# Controller_low_power_v1_0.net
KiCad netlist of a schematic drawn in EAGLE
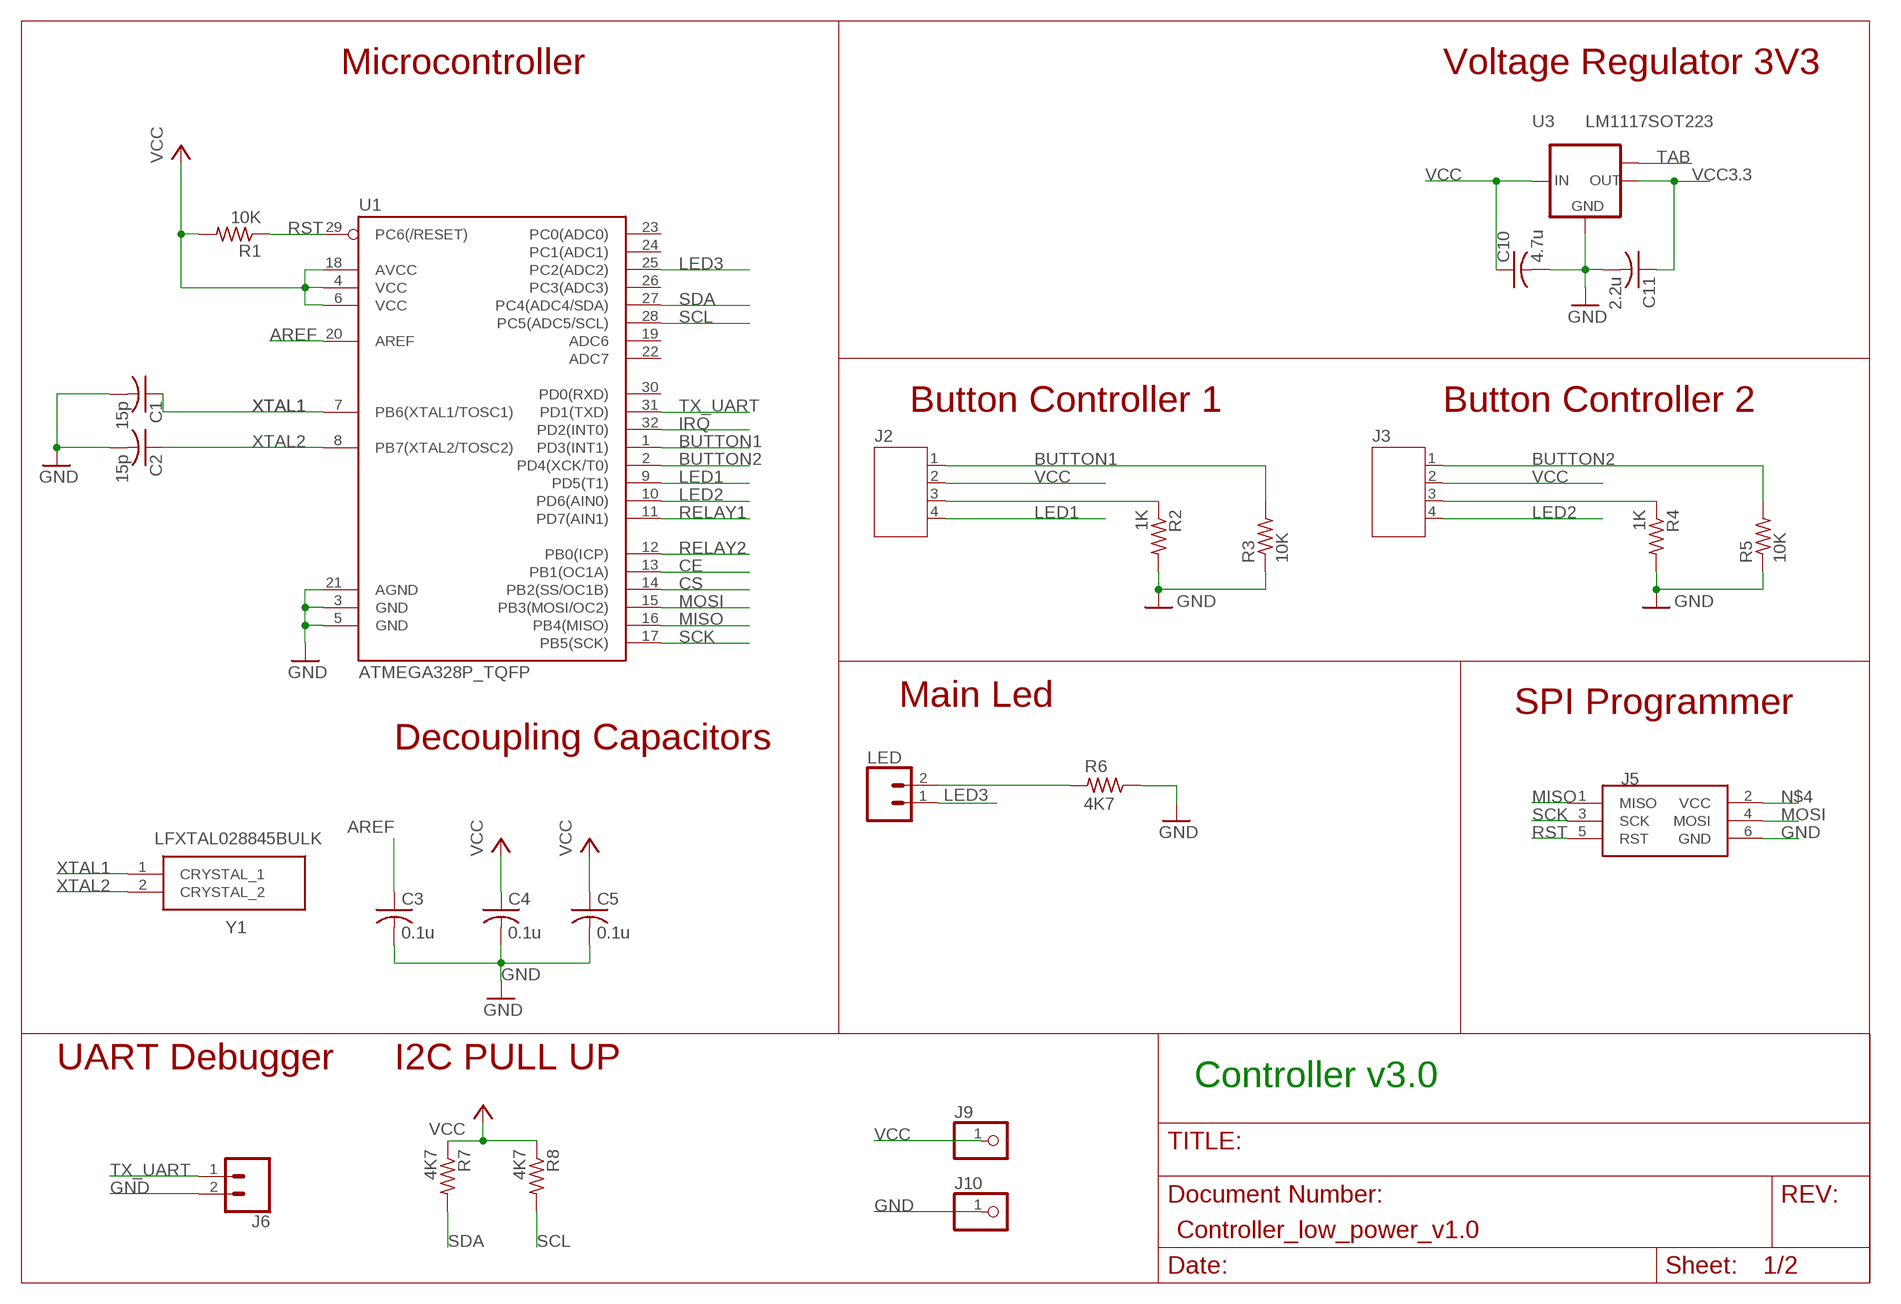
[diagram p0: schematic, sheet 1]
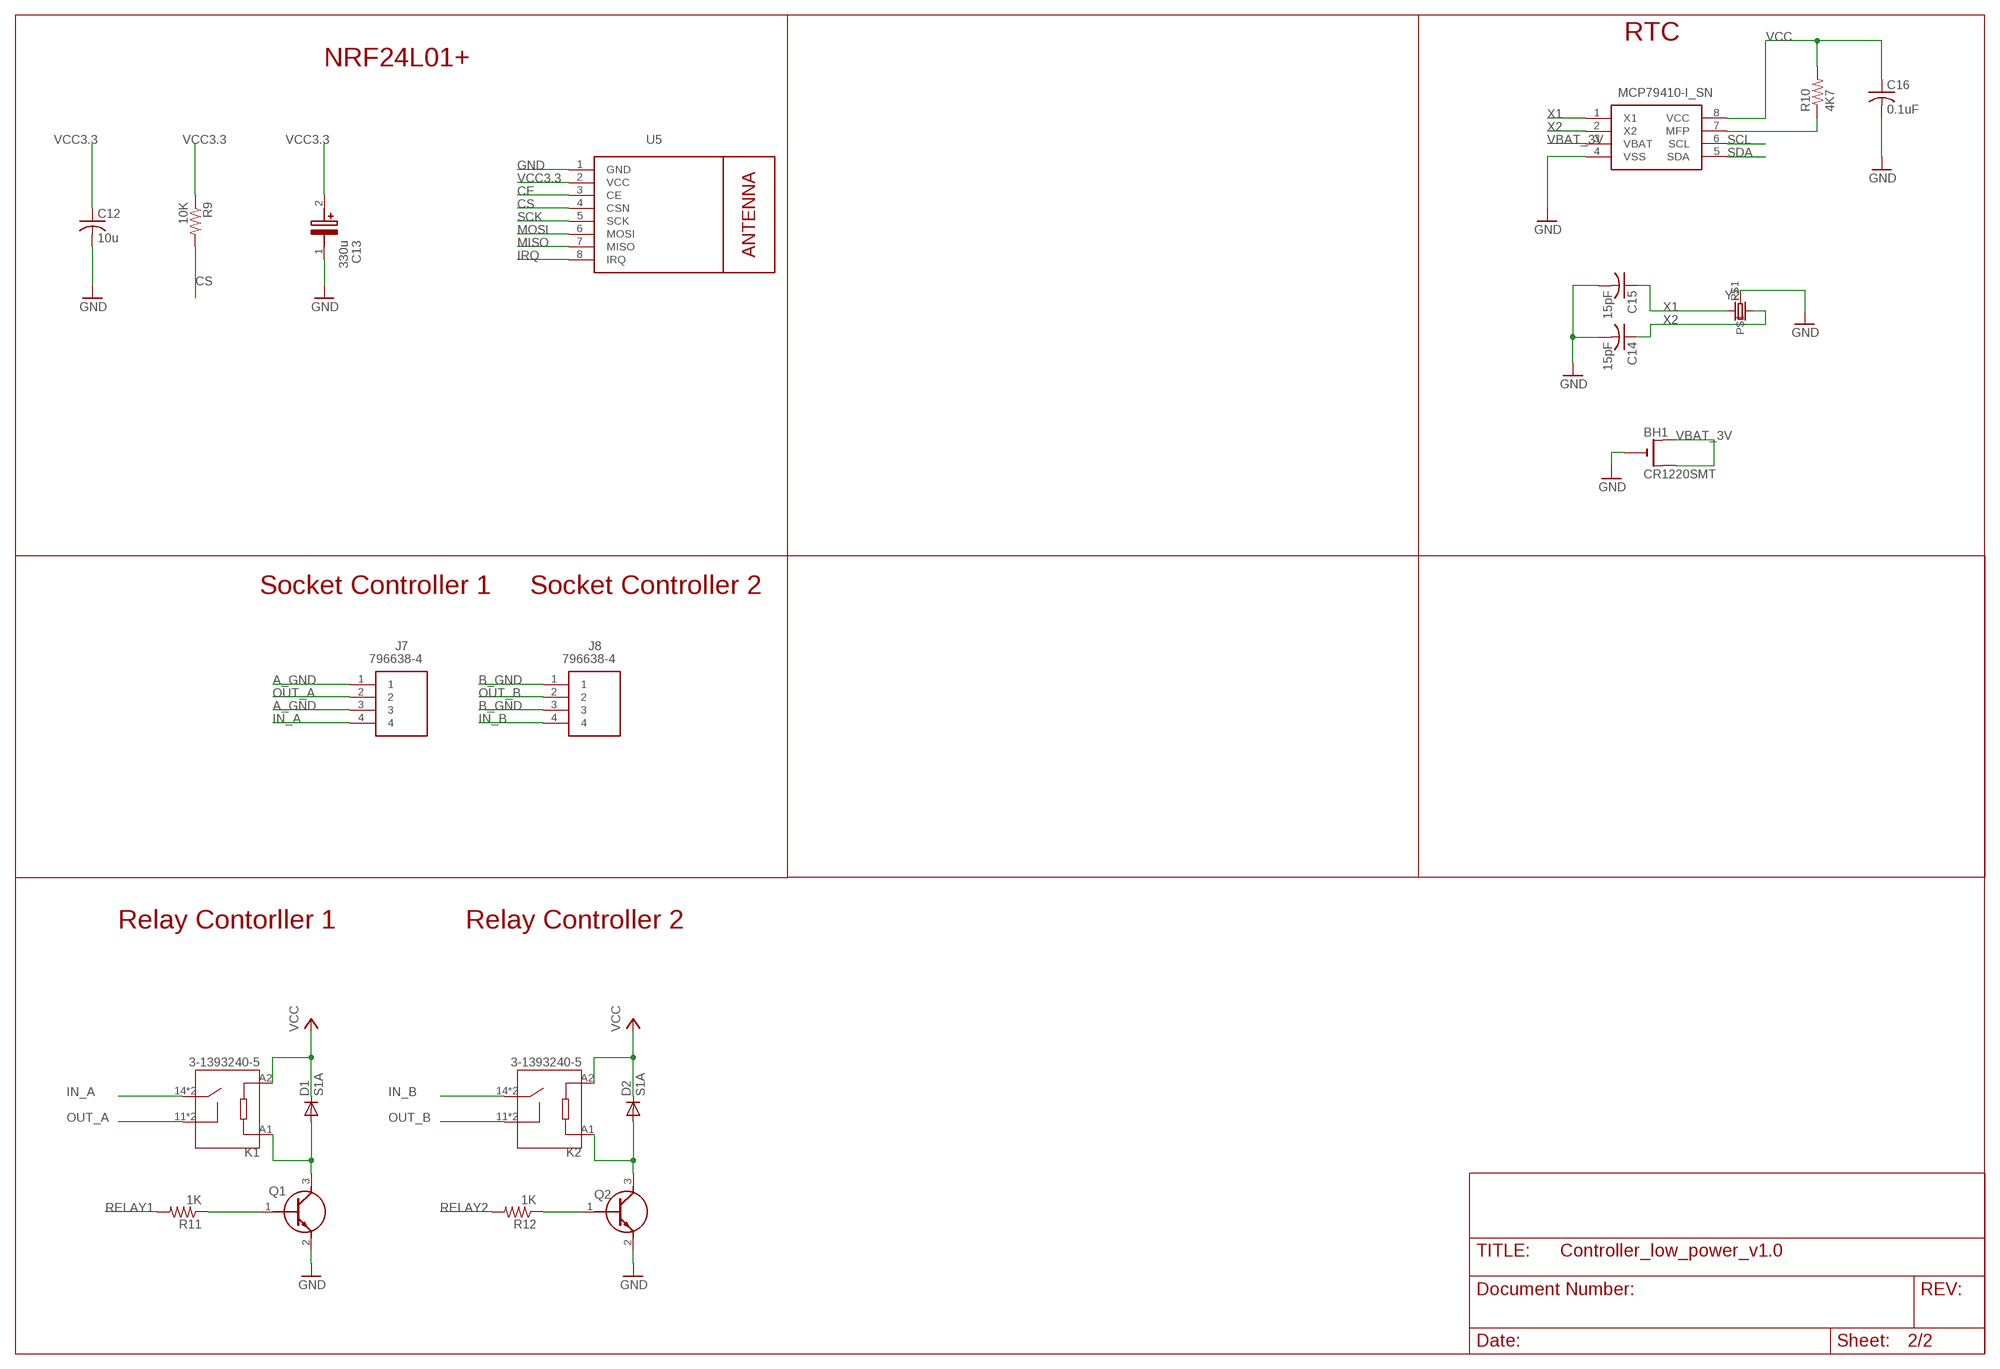
[diagram p1: schematic, sheet 2]

(export (version "E")
  (design (tool "Eeschema 10.0.6"))
  (components
    (comp (ref "C1")
      (value "15p")
      (footprint "eagle-import:SMD-0805")
      (libsource (lib "eagle-import") (part "CAPACITOR-SMD-0805"))
    )
    (comp (ref "C2")
      (value "15p")
      (footprint "eagle-import:SMD-0805")
      (libsource (lib "eagle-import") (part "CAPACITOR-SMD-0805"))
    )
    (comp (ref "C3")
      (value "0.1u")
      (footprint "eagle-import:SMD-0805")
      (libsource (lib "eagle-import") (part "CAPACITOR-SMD-0805"))
    )
    (comp (ref "C4")
      (value "0.1u")
      (footprint "eagle-import:SMD-0805")
      (libsource (lib "eagle-import") (part "CAPACITOR-SMD-0805"))
    )
    (comp (ref "C5")
      (value "0.1u")
      (footprint "eagle-import:SMD-0805")
      (libsource (lib "eagle-import") (part "CAPACITOR-SMD-0805"))
    )
    (comp (ref "C10")
      (value "4.7u")
      (footprint "eagle-import:SMD-0805")
      (libsource (lib "eagle-import") (part "CAPACITOR-SMD-0805"))
    )
    (comp (ref "C11")
      (value "2.2u")
      (footprint "eagle-import:SMD-0805")
      (libsource (lib "eagle-import") (part "CAPACITOR-SMD-0805"))
    )
    (comp (ref "J2")
      (value "JST-PH4")
      (footprint "eagle-import:JST-PH4")
      (libsource (lib "eagle-import") (part "JST-PH4"))
    )
    (comp (ref "J3")
      (value "JST-PH4")
      (footprint "eagle-import:JST-PH4")
      (libsource (lib "eagle-import") (part "JST-PH4"))
    )
    (comp (ref "J5")
      (value "ISP")
      (footprint "eagle-import:AVRISP")
      (libsource (lib "eagle-import") (part "AVRISP-6"))
    )
    (comp (ref "J6")
      (value "CONN_02")
      (footprint "eagle-import:1X02")
      (libsource (lib "eagle-import") (part "CONN_02"))
    )
    (comp (ref "J9")
      (value "PINHD-1X1CB")
      (footprint "eagle-import:1X01-CLEANBIG")
      (libsource (lib "eagle-import") (part "PINHD-1X1CB"))
    )
    (comp (ref "J10")
      (value "PINHD-1X1CB")
      (footprint "eagle-import:1X01-CLEANBIG")
      (libsource (lib "eagle-import") (part "PINHD-1X1CB"))
    )
    (comp (ref "LED")
      (value "CONN_02")
      (footprint "eagle-import:1X02")
      (libsource (lib "eagle-import") (part "CONN_02"))
    )
    (comp (ref "R1")
      (value "10K")
      (footprint "eagle-import:SMD-0805")
      (libsource (lib "eagle-import") (part "RESISTOR-SMD-0805"))
    )
    (comp (ref "R2")
      (value "1K")
      (footprint "eagle-import:SMD-0805")
      (libsource (lib "eagle-import") (part "RESISTOR-SMD-0805"))
    )
    (comp (ref "R3")
      (value "10K")
      (footprint "eagle-import:SMD-0805")
      (libsource (lib "eagle-import") (part "RESISTOR-SMD-0805"))
    )
    (comp (ref "R4")
      (value "1K")
      (footprint "eagle-import:SMD-0805")
      (libsource (lib "eagle-import") (part "RESISTOR-SMD-0805"))
    )
    (comp (ref "R5")
      (value "10K")
      (footprint "eagle-import:SMD-0805")
      (libsource (lib "eagle-import") (part "RESISTOR-SMD-0805"))
    )
    (comp (ref "R6")
      (value "4K7")
      (footprint "eagle-import:SMD-0805")
      (libsource (lib "eagle-import") (part "RESISTOR-SMD-0805"))
    )
    (comp (ref "R7")
      (value "4K7")
      (footprint "eagle-import:SMD-0805")
      (libsource (lib "eagle-import") (part "RESISTOR-SMD-0805"))
    )
    (comp (ref "R8")
      (value "4K7")
      (footprint "eagle-import:SMD-0805")
      (libsource (lib "eagle-import") (part "RESISTOR-SMD-0805"))
    )
    (comp (ref "U1")
      (value "ATMEGA328P_TQFP")
      (footprint "eagle-import:TQFP32-08")
      (libsource (lib "eagle-import") (part "ATMEGA328P_TQFP"))
    )
    (comp (ref "U3")
      (value "LM1117SOT223")
      (footprint "eagle-import:SOT223")
      (libsource (lib "eagle-import") (part "LM1117MPX-3.3"))
    )
    (comp (ref "Y1")
      (value "LFXTAL028845BULK")
      (footprint "eagle-import:LFXTAL028845BULK")
      (libsource (lib "eagle-import") (part "LFXTAL028845BULK"))
    )
    (comp (ref "BH1")
      (value "CR1220SMT")
      (footprint "eagle-import:CR1220-SMD")
      (fields (field (name "MF") "FDK America,") (field (name "MP") "CR1220"))
      (libsource (lib "eagle-import") (part "CR1220SMT"))
    )
    (comp (ref "C12")
      (value "10u")
      (footprint "eagle-import:SMD-0805")
      (libsource (lib "eagle-import") (part "CAPACITOR-SMD-0805"))
    )
    (comp (ref "C13")
      (value "330u")
      (footprint "eagle-import:SMD_LYTIC_D8")
      (fields
        (field (name "MANUFACTURER_PART_NUMBER") "EEE-FNC271XUP")
        (field (name "MOUSER_PART_NUMBER") "667-EEE-FNC271XUP")
      )
      (libsource (lib "eagle-import") (part "EEE-FNC271XUP"))
    )
    (comp (ref "C14")
      (value "15pF")
      (footprint "eagle-import:SMD-0805")
      (libsource (lib "eagle-import") (part "CAPACITOR-SMD-0805"))
    )
    (comp (ref "C15")
      (value "15pF")
      (footprint "eagle-import:SMD-0805")
      (libsource (lib "eagle-import") (part "CAPACITOR-SMD-0805"))
    )
    (comp (ref "C16")
      (value "0.1uF")
      (footprint "eagle-import:SMD-0805")
      (libsource (lib "eagle-import") (part "CAPACITOR-SMD-0805"))
    )
    (comp (ref "D1")
      (value "S1A")
      (footprint "eagle-import:DO214AC")
      (fields (field (name "MF") "Fairchild"))
      (libsource (lib "eagle-import") (part "S1A"))
    )
    (comp (ref "D2")
      (value "S1A")
      (footprint "eagle-import:DO214AC")
      (fields (field (name "MF") "Fairchild"))
      (libsource (lib "eagle-import") (part "S1A"))
    )
    (comp (ref "J7")
      (value "796638-4")
      (footprint "eagle-import:SHDRRA4W102P0X508_1X4_2214X120")
      (fields (field (name "MOUSER_PART_NUMBER") "571-7966384"))
      (libsource (lib "eagle-import") (part "796638-4"))
    )
    (comp (ref "J8")
      (value "796638-4")
      (footprint "eagle-import:SHDRRA4W102P0X508_1X4_2214X120")
      (fields (field (name "MOUSER_PART_NUMBER") "571-7966384"))
      (libsource (lib "eagle-import") (part "796638-4"))
    )
    (comp (ref "K1")
      (value "3-1393240-5")
      (footprint "eagle-import:TE_3-1393240-5")
      (fields (field (name "MF") "TE Connectivity"))
      (libsource (lib "eagle-import") (part "3-1393240-5"))
    )
    (comp (ref "K2")
      (value "3-1393240-5")
      (footprint "eagle-import:TE_3-1393240-5")
      (fields (field (name "MF") "TE Connectivity"))
      (libsource (lib "eagle-import") (part "3-1393240-5"))
    )
    (comp (ref "Q1")
      (value "MMBT2222A-TP")
      (footprint "eagle-import:SI2305TP")
      (fields (field (name "MOUSER_PART_NUMBER") "833-MMBT2222A-TP"))
      (libsource (lib "eagle-import") (part "MMBT2222A-TP"))
    )
    (comp (ref "Q2")
      (value "MMBT2222A-TP")
      (footprint "eagle-import:SI2305TP")
      (fields (field (name "MOUSER_PART_NUMBER") "833-MMBT2222A-TP"))
      (libsource (lib "eagle-import") (part "MMBT2222A-TP"))
    )
    (comp (ref "R9")
      (value "10K")
      (footprint "eagle-import:SMD-0805")
      (libsource (lib "eagle-import") (part "RESISTOR-SMD-0805"))
    )
    (comp (ref "R10")
      (value "4K7")
      (footprint "eagle-import:SMD-0805")
      (libsource (lib "eagle-import") (part "RESISTOR-SMD-0805"))
    )
    (comp (ref "R11")
      (value "1K")
      (footprint "eagle-import:SMD-0805")
      (libsource (lib "eagle-import") (part "RESISTOR-SMD-0805"))
    )
    (comp (ref "R12")
      (value "1K")
      (footprint "eagle-import:SMD-0805")
      (libsource (lib "eagle-import") (part "RESISTOR-SMD-0805"))
    )
    (comp (ref "U5")
      (value "WIRELESS-NRF24L01")
      (footprint "eagle-import:WIRELESS-NRF24L01")
      (libsource (lib "eagle-import") (part "WIRELESS-NRF24L01"))
    )
    (comp (ref "U6")
      (value "MCP79410-I_SN")
      (footprint "eagle-import:SOIC127P600X175-8N")
      (fields
        (field (name "MANUFACTURER_PART_NUMBER") "MCP79410-I/SN")
        (field (name "MOUSER_PART_NUMBER") "579-MCP79410-I/SN")
      )
      (libsource (lib "eagle-import") (part "MCP79410-I_SN"))
    )
    (comp (ref "Y2")
      (value "CRYSTALTC26H")
      (footprint "eagle-import:TC26H")
      (libsource (lib "eagle-import") (part "CRYSTALTC26H"))
    )
  )
  (nets
    (net (code "1") (name "AREF") (class "Default")
      (node (ref "C3") (pin "1") (pinfunction "1_1") (pintype "passive"))
      (node (ref "U1") (pin "20") (pinfunction "AREF_20") (pintype "bidirectional"))
    )
    (net (code "2") (name "A_GND") (class "Default")
      (node (ref "J7") (pin "1") (pinfunction "1_1") (pintype "bidirectional"))
      (node (ref "J7") (pin "3") (pinfunction "3_3") (pintype "bidirectional"))
    )
    (net (code "3") (name "BUTTON1") (class "Default")
      (node (ref "J2") (pin "1") (pinfunction "1_1") (pintype "passive"))
      (node (ref "R3") (pin "2") (pinfunction "2_2") (pintype "passive"))
      (node (ref "U1") (pin "1") (pinfunction "PD3(INT1)_1") (pintype "bidirectional"))
    )
    (net (code "4") (name "BUTTON2") (class "Default")
      (node (ref "J3") (pin "1") (pinfunction "1_1") (pintype "passive"))
      (node (ref "R5") (pin "2") (pinfunction "2_2") (pintype "passive"))
      (node (ref "U1") (pin "2") (pinfunction "PD4(XCK/T0)_2") (pintype "bidirectional"))
    )
    (net (code "5") (name "B_GND") (class "Default")
      (node (ref "J8") (pin "1") (pinfunction "1_1") (pintype "bidirectional"))
      (node (ref "J8") (pin "3") (pinfunction "3_3") (pintype "bidirectional"))
    )
    (net (code "6") (name "CE") (class "Default")
      (node (ref "U1") (pin "13") (pinfunction "PB1(OC1A)_13") (pintype "bidirectional"))
      (node (ref "U5") (pin "3") (pinfunction "CE_3") (pintype "bidirectional"))
    )
    (net (code "7") (name "CS") (class "Default")
      (node (ref "R9") (pin "2") (pinfunction "2_2") (pintype "passive"))
      (node (ref "U1") (pin "14") (pinfunction "PB2(SS/OC1B)_14") (pintype "bidirectional"))
      (node (ref "U5") (pin "4") (pinfunction "CSN_4") (pintype "bidirectional"))
    )
    (net (code "8") (name "GND") (class "Default")
      (node (ref "BH1") (pin "-") (pinfunction "-_-") (pintype "passive"))
      (node (ref "C1") (pin "2") (pinfunction "2_2") (pintype "passive"))
      (node (ref "C10") (pin "2") (pinfunction "2_2") (pintype "passive"))
      (node (ref "C11") (pin "2") (pinfunction "2_2") (pintype "passive"))
      (node (ref "C12") (pin "2") (pinfunction "2_2") (pintype "passive"))
      (node (ref "C13") (pin "1") (pinfunction "1_1") (pintype "bidirectional"))
      (node (ref "C14") (pin "2") (pinfunction "2_2") (pintype "passive"))
      (node (ref "C15") (pin "2") (pinfunction "2_2") (pintype "passive"))
      (node (ref "C16") (pin "2") (pinfunction "2_2") (pintype "passive"))
      (node (ref "C2") (pin "2") (pinfunction "2_2") (pintype "passive"))
      (node (ref "C3") (pin "2") (pinfunction "2_2") (pintype "passive"))
      (node (ref "C4") (pin "2") (pinfunction "2_2") (pintype "passive"))
      (node (ref "C5") (pin "2") (pinfunction "2_2") (pintype "passive"))
      (node (ref "J10") (pin "1") (pinfunction "1_1") (pintype "passive"))
      (node (ref "J5") (pin "6") (pinfunction "GND_6") (pintype "power_in"))
      (node (ref "J6") (pin "2") (pinfunction "2_2") (pintype "passive"))
      (node (ref "Q1") (pin "2") (pinfunction "E_2") (pintype "bidirectional"))
      (node (ref "Q2") (pin "2") (pinfunction "E_2") (pintype "bidirectional"))
      (node (ref "R2") (pin "2") (pinfunction "2_2") (pintype "passive"))
      (node (ref "R3") (pin "1") (pinfunction "1_1") (pintype "passive"))
      (node (ref "R4") (pin "2") (pinfunction "2_2") (pintype "passive"))
      (node (ref "R5") (pin "1") (pinfunction "1_1") (pintype "passive"))
      (node (ref "R6") (pin "1") (pinfunction "1_1") (pintype "passive"))
      (node (ref "U1") (pin "21") (pinfunction "AGND_21") (pintype "bidirectional"))
      (node (ref "U1") (pin "3") (pinfunction "GND_3") (pintype "bidirectional"))
      (node (ref "U1") (pin "5") (pinfunction "GND_5") (pintype "bidirectional"))
      (node (ref "U3") (pin "1") (pinfunction "GND_1") (pintype "input"))
      (node (ref "U5") (pin "1") (pinfunction "GND_1") (pintype "power_in"))
      (node (ref "U6") (pin "4") (pinfunction "VSS_4") (pintype "power_in"))
      (node (ref "Y2") (pin "P$1") (pinfunction "P$1_P$1") (pintype "passive"))
    )
    (net (code "9") (name "IN_A") (class "Default")
      (node (ref "J7") (pin "4") (pinfunction "4_4") (pintype "bidirectional"))
      (node (ref "K1") (pin "14") (pinfunction "14_14") (pintype "passive"))
      (node (ref "K1") (pin "14-1") (pinfunction "14_14-1") (pintype "passive"))
    )
    (net (code "10") (name "IN_B") (class "Default")
      (node (ref "J8") (pin "4") (pinfunction "4_4") (pintype "bidirectional"))
      (node (ref "K2") (pin "14") (pinfunction "14_14") (pintype "passive"))
      (node (ref "K2") (pin "14-1") (pinfunction "14_14-1") (pintype "passive"))
    )
    (net (code "11") (name "IRQ") (class "Default")
      (node (ref "U1") (pin "32") (pinfunction "PD2(INT0)_32") (pintype "bidirectional"))
      (node (ref "U5") (pin "8") (pinfunction "IRQ_8") (pintype "bidirectional"))
    )
    (net (code "12") (name "LED1") (class "Default")
      (node (ref "J2") (pin "4") (pinfunction "4_4") (pintype "passive"))
      (node (ref "U1") (pin "9") (pinfunction "PD5(T1)_9") (pintype "bidirectional"))
    )
    (net (code "13") (name "LED2") (class "Default")
      (node (ref "J3") (pin "4") (pinfunction "4_4") (pintype "passive"))
      (node (ref "U1") (pin "10") (pinfunction "PD6(AIN0)_10") (pintype "bidirectional"))
    )
    (net (code "14") (name "LED3") (class "Default")
      (node (ref "LED") (pin "1") (pinfunction "1_1") (pintype "passive"))
      (node (ref "U1") (pin "25") (pinfunction "PC2(ADC2)_25") (pintype "bidirectional"))
    )
    (net (code "15") (name "MISO") (class "Default")
      (node (ref "J5") (pin "1") (pinfunction "MISO_1") (pintype "input"))
      (node (ref "U1") (pin "16") (pinfunction "PB4(MISO)_16") (pintype "bidirectional"))
      (node (ref "U5") (pin "7") (pinfunction "MISO_7") (pintype "bidirectional"))
    )
    (net (code "16") (name "MOSI") (class "Default")
      (node (ref "J5") (pin "4") (pinfunction "MOSI_4") (pintype "output"))
      (node (ref "U1") (pin "15") (pinfunction "PB3(MOSI/OC2)_15") (pintype "bidirectional"))
      (node (ref "U5") (pin "6") (pinfunction "MOSI_6") (pintype "bidirectional"))
    )
    (net (code "17") (name "N$4") (class "Default")
      (node (ref "J5") (pin "2") (pinfunction "VCC_2") (pintype "power_in"))
    )
    (net (code "18") (name "Net-(J2-Pad3)") (class "Default")
      (node (ref "J2") (pin "3") (pinfunction "3_3") (pintype "passive"))
      (node (ref "R2") (pin "1") (pinfunction "1_1") (pintype "passive"))
    )
    (net (code "19") (name "Net-(J3-Pad3)") (class "Default")
      (node (ref "J3") (pin "3") (pinfunction "3_3") (pintype "passive"))
      (node (ref "R4") (pin "1") (pinfunction "1_1") (pintype "passive"))
    )
    (net (code "20") (name "Net-(LED-Pad2)") (class "Default")
      (node (ref "LED") (pin "2") (pinfunction "2_2") (pintype "passive"))
      (node (ref "R6") (pin "2") (pinfunction "2_2") (pintype "passive"))
    )
    (net (code "21") (name "Net-(Q1-B)") (class "Default")
      (node (ref "Q1") (pin "1") (pinfunction "B_1") (pintype "bidirectional"))
      (node (ref "R11") (pin "1") (pinfunction "1_1") (pintype "passive"))
    )
    (net (code "22") (name "Net-(Q1-C)") (class "Default")
      (node (ref "D1") (pin "A") (pinfunction "A_A") (pintype "passive"))
      (node (ref "K1") (pin "A1") (pinfunction "A1_A1") (pintype "passive"))
      (node (ref "Q1") (pin "3") (pinfunction "C_3") (pintype "bidirectional"))
    )
    (net (code "23") (name "Net-(Q2-B)") (class "Default")
      (node (ref "Q2") (pin "1") (pinfunction "B_1") (pintype "bidirectional"))
      (node (ref "R12") (pin "1") (pinfunction "1_1") (pintype "passive"))
    )
    (net (code "24") (name "Net-(Q2-C)") (class "Default")
      (node (ref "D2") (pin "A") (pinfunction "A_A") (pintype "passive"))
      (node (ref "K2") (pin "A1") (pinfunction "A1_A1") (pintype "passive"))
      (node (ref "Q2") (pin "3") (pinfunction "C_3") (pintype "bidirectional"))
    )
    (net (code "25") (name "Net-(U6-MFP)") (class "Default")
      (node (ref "R10") (pin "1") (pinfunction "1_1") (pintype "passive"))
      (node (ref "U6") (pin "7") (pinfunction "MFP_7") (pintype "bidirectional"))
    )
    (net (code "26") (name "OUT_A") (class "Default")
      (node (ref "J7") (pin "2") (pinfunction "2_2") (pintype "bidirectional"))
      (node (ref "K1") (pin "11") (pinfunction "11_11") (pintype "passive"))
      (node (ref "K1") (pin "11-1") (pinfunction "11_11-1") (pintype "passive"))
    )
    (net (code "27") (name "OUT_B") (class "Default")
      (node (ref "J8") (pin "2") (pinfunction "2_2") (pintype "bidirectional"))
      (node (ref "K2") (pin "11") (pinfunction "11_11") (pintype "passive"))
      (node (ref "K2") (pin "11-1") (pinfunction "11_11-1") (pintype "passive"))
    )
    (net (code "28") (name "RELAY1") (class "Default")
      (node (ref "R11") (pin "2") (pinfunction "2_2") (pintype "passive"))
      (node (ref "U1") (pin "11") (pinfunction "PD7(AIN1)_11") (pintype "bidirectional"))
    )
    (net (code "29") (name "RELAY2") (class "Default")
      (node (ref "R12") (pin "2") (pinfunction "2_2") (pintype "passive"))
      (node (ref "U1") (pin "12") (pinfunction "PB0(ICP)_12") (pintype "bidirectional"))
    )
    (net (code "30") (name "RST") (class "Default")
      (node (ref "J5") (pin "5") (pinfunction "RST_5") (pintype "output"))
      (node (ref "R1") (pin "1") (pinfunction "1_1") (pintype "passive"))
      (node (ref "U1") (pin "29") (pinfunction "PC6(/RESET)_29") (pintype "bidirectional"))
    )
    (net (code "31") (name "SCK") (class "Default")
      (node (ref "J5") (pin "3") (pinfunction "SCK_3") (pintype "output"))
      (node (ref "U1") (pin "17") (pinfunction "PB5(SCK)_17") (pintype "bidirectional"))
      (node (ref "U5") (pin "5") (pinfunction "SCK_5") (pintype "bidirectional"))
    )
    (net (code "32") (name "SCL") (class "Default")
      (node (ref "R8") (pin "2") (pinfunction "2_2") (pintype "passive"))
      (node (ref "U1") (pin "28") (pinfunction "PC5(ADC5/SCL)_28") (pintype "bidirectional"))
      (node (ref "U6") (pin "6") (pinfunction "SCL_6") (pintype "bidirectional"))
    )
    (net (code "33") (name "SDA") (class "Default")
      (node (ref "R7") (pin "2") (pinfunction "2_2") (pintype "passive"))
      (node (ref "U1") (pin "27") (pinfunction "PC4(ADC4/SDA)_27") (pintype "bidirectional"))
      (node (ref "U6") (pin "5") (pinfunction "SDA_5") (pintype "bidirectional"))
    )
    (net (code "34") (name "TAB") (class "Default")
      (node (ref "U3") (pin "TAB") (pinfunction "OUT1_TAB") (pintype "passive"))
    )
    (net (code "35") (name "TX_UART") (class "Default")
      (node (ref "J6") (pin "1") (pinfunction "1_1") (pintype "passive"))
      (node (ref "U1") (pin "31") (pinfunction "PD1(TXD)_31") (pintype "bidirectional"))
    )
    (net (code "36") (name "VBAT_3V") (class "Default")
      (node (ref "BH1") (pin "+$1") (pinfunction "+_+$1") (pintype "passive"))
      (node (ref "BH1") (pin "+$2") (pinfunction "+1_+$2") (pintype "passive"))
      (node (ref "U6") (pin "3") (pinfunction "VBAT_3") (pintype "bidirectional"))
    )
    (net (code "37") (name "VCC") (class "Default")
      (node (ref "C10") (pin "1") (pinfunction "1_1") (pintype "passive"))
      (node (ref "C16") (pin "1") (pinfunction "1_1") (pintype "passive"))
      (node (ref "C4") (pin "1") (pinfunction "1_1") (pintype "passive"))
      (node (ref "C5") (pin "1") (pinfunction "1_1") (pintype "passive"))
      (node (ref "D1") (pin "C") (pinfunction "C_C") (pintype "passive"))
      (node (ref "D2") (pin "C") (pinfunction "C_C") (pintype "passive"))
      (node (ref "J2") (pin "2") (pinfunction "2_2") (pintype "passive"))
      (node (ref "J3") (pin "2") (pinfunction "2_2") (pintype "passive"))
      (node (ref "J9") (pin "1") (pinfunction "1_1") (pintype "passive"))
      (node (ref "K1") (pin "A2") (pinfunction "A2_A2") (pintype "passive"))
      (node (ref "K2") (pin "A2") (pinfunction "A2_A2") (pintype "passive"))
      (node (ref "R1") (pin "2") (pinfunction "2_2") (pintype "passive"))
      (node (ref "R10") (pin "2") (pinfunction "2_2") (pintype "passive"))
      (node (ref "R7") (pin "1") (pinfunction "1_1") (pintype "passive"))
      (node (ref "R8") (pin "1") (pinfunction "1_1") (pintype "passive"))
      (node (ref "U1") (pin "18") (pinfunction "AVCC_18") (pintype "bidirectional"))
      (node (ref "U1") (pin "4") (pinfunction "VCC_4") (pintype "bidirectional"))
      (node (ref "U1") (pin "6") (pinfunction "VCC_6") (pintype "bidirectional"))
      (node (ref "U3") (pin "3") (pinfunction "IN_3") (pintype "input"))
      (node (ref "U6") (pin "8") (pinfunction "VCC_8") (pintype "power_in"))
    )
    (net (code "38") (name "VCC3.3") (class "Default")
      (node (ref "C11") (pin "1") (pinfunction "1_1") (pintype "passive"))
      (node (ref "C12") (pin "1") (pinfunction "1_1") (pintype "passive"))
      (node (ref "C13") (pin "2") (pinfunction "2_2") (pintype "bidirectional"))
      (node (ref "R9") (pin "1") (pinfunction "1_1") (pintype "passive"))
      (node (ref "U3") (pin "2") (pinfunction "OUT_2") (pintype "passive"))
      (node (ref "U5") (pin "2") (pinfunction "VCC_2") (pintype "power_in"))
    )
    (net (code "39") (name "X1") (class "Default")
      (node (ref "C15") (pin "1") (pinfunction "1_1") (pintype "passive"))
      (node (ref "U6") (pin "1") (pinfunction "X1_1") (pintype "bidirectional"))
      (node (ref "Y2") (pin "2") (pinfunction "2_2") (pintype "passive"))
    )
    (net (code "40") (name "X2") (class "Default")
      (node (ref "C14") (pin "1") (pinfunction "1_1") (pintype "passive"))
      (node (ref "U6") (pin "2") (pinfunction "X2_2") (pintype "bidirectional"))
      (node (ref "Y2") (pin "1") (pinfunction "1_1") (pintype "passive"))
    )
    (net (code "41") (name "XTAL1") (class "Default")
      (node (ref "C1") (pin "1") (pinfunction "1_1") (pintype "passive"))
      (node (ref "U1") (pin "7") (pinfunction "PB6(XTAL1/TOSC1)_7") (pintype "bidirectional"))
      (node (ref "Y1") (pin "1") (pinfunction "CRYSTAL_1_1") (pintype "bidirectional"))
    )
    (net (code "42") (name "XTAL2") (class "Default")
      (node (ref "C2") (pin "1") (pinfunction "1_1") (pintype "passive"))
      (node (ref "U1") (pin "8") (pinfunction "PB7(XTAL2/TOSC2)_8") (pintype "bidirectional"))
      (node (ref "Y1") (pin "2") (pinfunction "CRYSTAL_2_2") (pintype "bidirectional"))
    )
    (net (code "43") (name "unconnected-(U1-ADC6-Pad19)") (class "Default")
      (node (ref "U1") (pin "19") (pinfunction "ADC6_19") (pintype "bidirectional"))
    )
    (net (code "44") (name "unconnected-(U1-ADC7-Pad22)") (class "Default")
      (node (ref "U1") (pin "22") (pinfunction "ADC7_22") (pintype "bidirectional"))
    )
    (net (code "45") (name "unconnected-(U1-PC0(ADC0)-Pad23)") (class "Default")
      (node (ref "U1") (pin "23") (pinfunction "PC0(ADC0)_23") (pintype "bidirectional"))
    )
    (net (code "46") (name "unconnected-(U1-PC1(ADC1)-Pad24)") (class "Default")
      (node (ref "U1") (pin "24") (pinfunction "PC1(ADC1)_24") (pintype "bidirectional"))
    )
    (net (code "47") (name "unconnected-(U1-PC3(ADC3)-Pad26)") (class "Default")
      (node (ref "U1") (pin "26") (pinfunction "PC3(ADC3)_26") (pintype "bidirectional"))
    )
    (net (code "48") (name "unconnected-(U1-PD0(RXD)-Pad30)") (class "Default")
      (node (ref "U1") (pin "30") (pinfunction "PD0(RXD)_30") (pintype "bidirectional"))
    )
  )
)
